# FSR_Input_MCP602.net
KiCad netlist of a schematic drawn in EAGLE
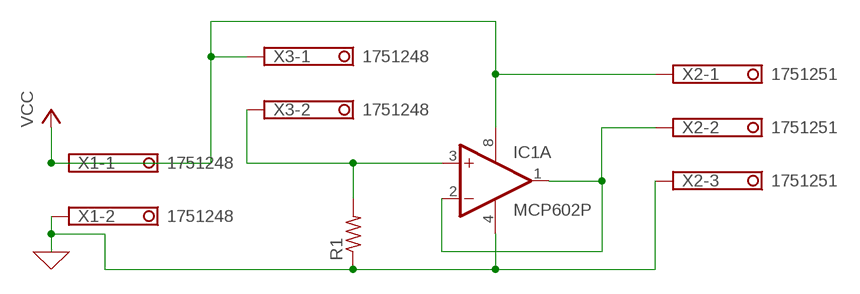
[diagram p0: schematic, sheet 1]

(export (version "E")
  (design (tool "Eeschema 10.0.6"))
  (components
    (comp (ref "IC1")
      (value "MCP602P")
      (footprint "eagle-import:DIL08")
      (libsource (lib "eagle-import") (part "MCP602P"))
    )
    (comp (ref "R1")
      (value "R-US_0204/5")
      (footprint "eagle-import:0204_5")
      (libsource (lib "eagle-import") (part "R-US_0204/5"))
    )
    (comp (ref "X1")
      (value "1751248")
      (footprint "eagle-import:1751248")
      (libsource (lib "eagle-import") (part "1751248"))
    )
    (comp (ref "X2")
      (value "1751251")
      (footprint "eagle-import:1751251")
      (libsource (lib "eagle-import") (part "1751251"))
    )
    (comp (ref "X3")
      (value "1751248")
      (footprint "eagle-import:1751248")
      (libsource (lib "eagle-import") (part "1751248"))
    )
  )
  (nets
    (net (code "1") (name "GND") (class "Default")
      (node (ref "IC1") (pin "4") (pinfunction "V-_4") (pintype "power_in"))
      (node (ref "R1") (pin "1") (pinfunction "1_1") (pintype "passive"))
      (node (ref "X1") (pin "2") (pinfunction "K_2") (pintype "passive"))
      (node (ref "X2") (pin "3") (pinfunction "K_3") (pintype "passive"))
    )
    (net (code "2") (name "Net-(IC1A-+IN)") (class "Default")
      (node (ref "IC1") (pin "3") (pinfunction "+IN_3") (pintype "input"))
      (node (ref "R1") (pin "2") (pinfunction "2_2") (pintype "passive"))
      (node (ref "X3") (pin "2") (pinfunction "K_2") (pintype "passive"))
    )
    (net (code "3") (name "Net-(IC1A--IN)") (class "Default")
      (node (ref "IC1") (pin "1") (pinfunction "OUT_1") (pintype "output"))
      (node (ref "IC1") (pin "2") (pinfunction "-IN_2") (pintype "input"))
      (node (ref "X2") (pin "2") (pinfunction "K_2") (pintype "passive"))
    )
    (net (code "4") (name "VCC") (class "Default")
      (node (ref "IC1") (pin "8") (pinfunction "V+_8") (pintype "power_in"))
      (node (ref "X1") (pin "1") (pinfunction "K_1") (pintype "passive"))
      (node (ref "X2") (pin "1") (pinfunction "K_1") (pintype "passive"))
      (node (ref "X3") (pin "1") (pinfunction "K_1") (pintype "passive"))
    )
  )
)
